# Sheet1.net
KiCad netlist of a schematic drawn in Altium Designer
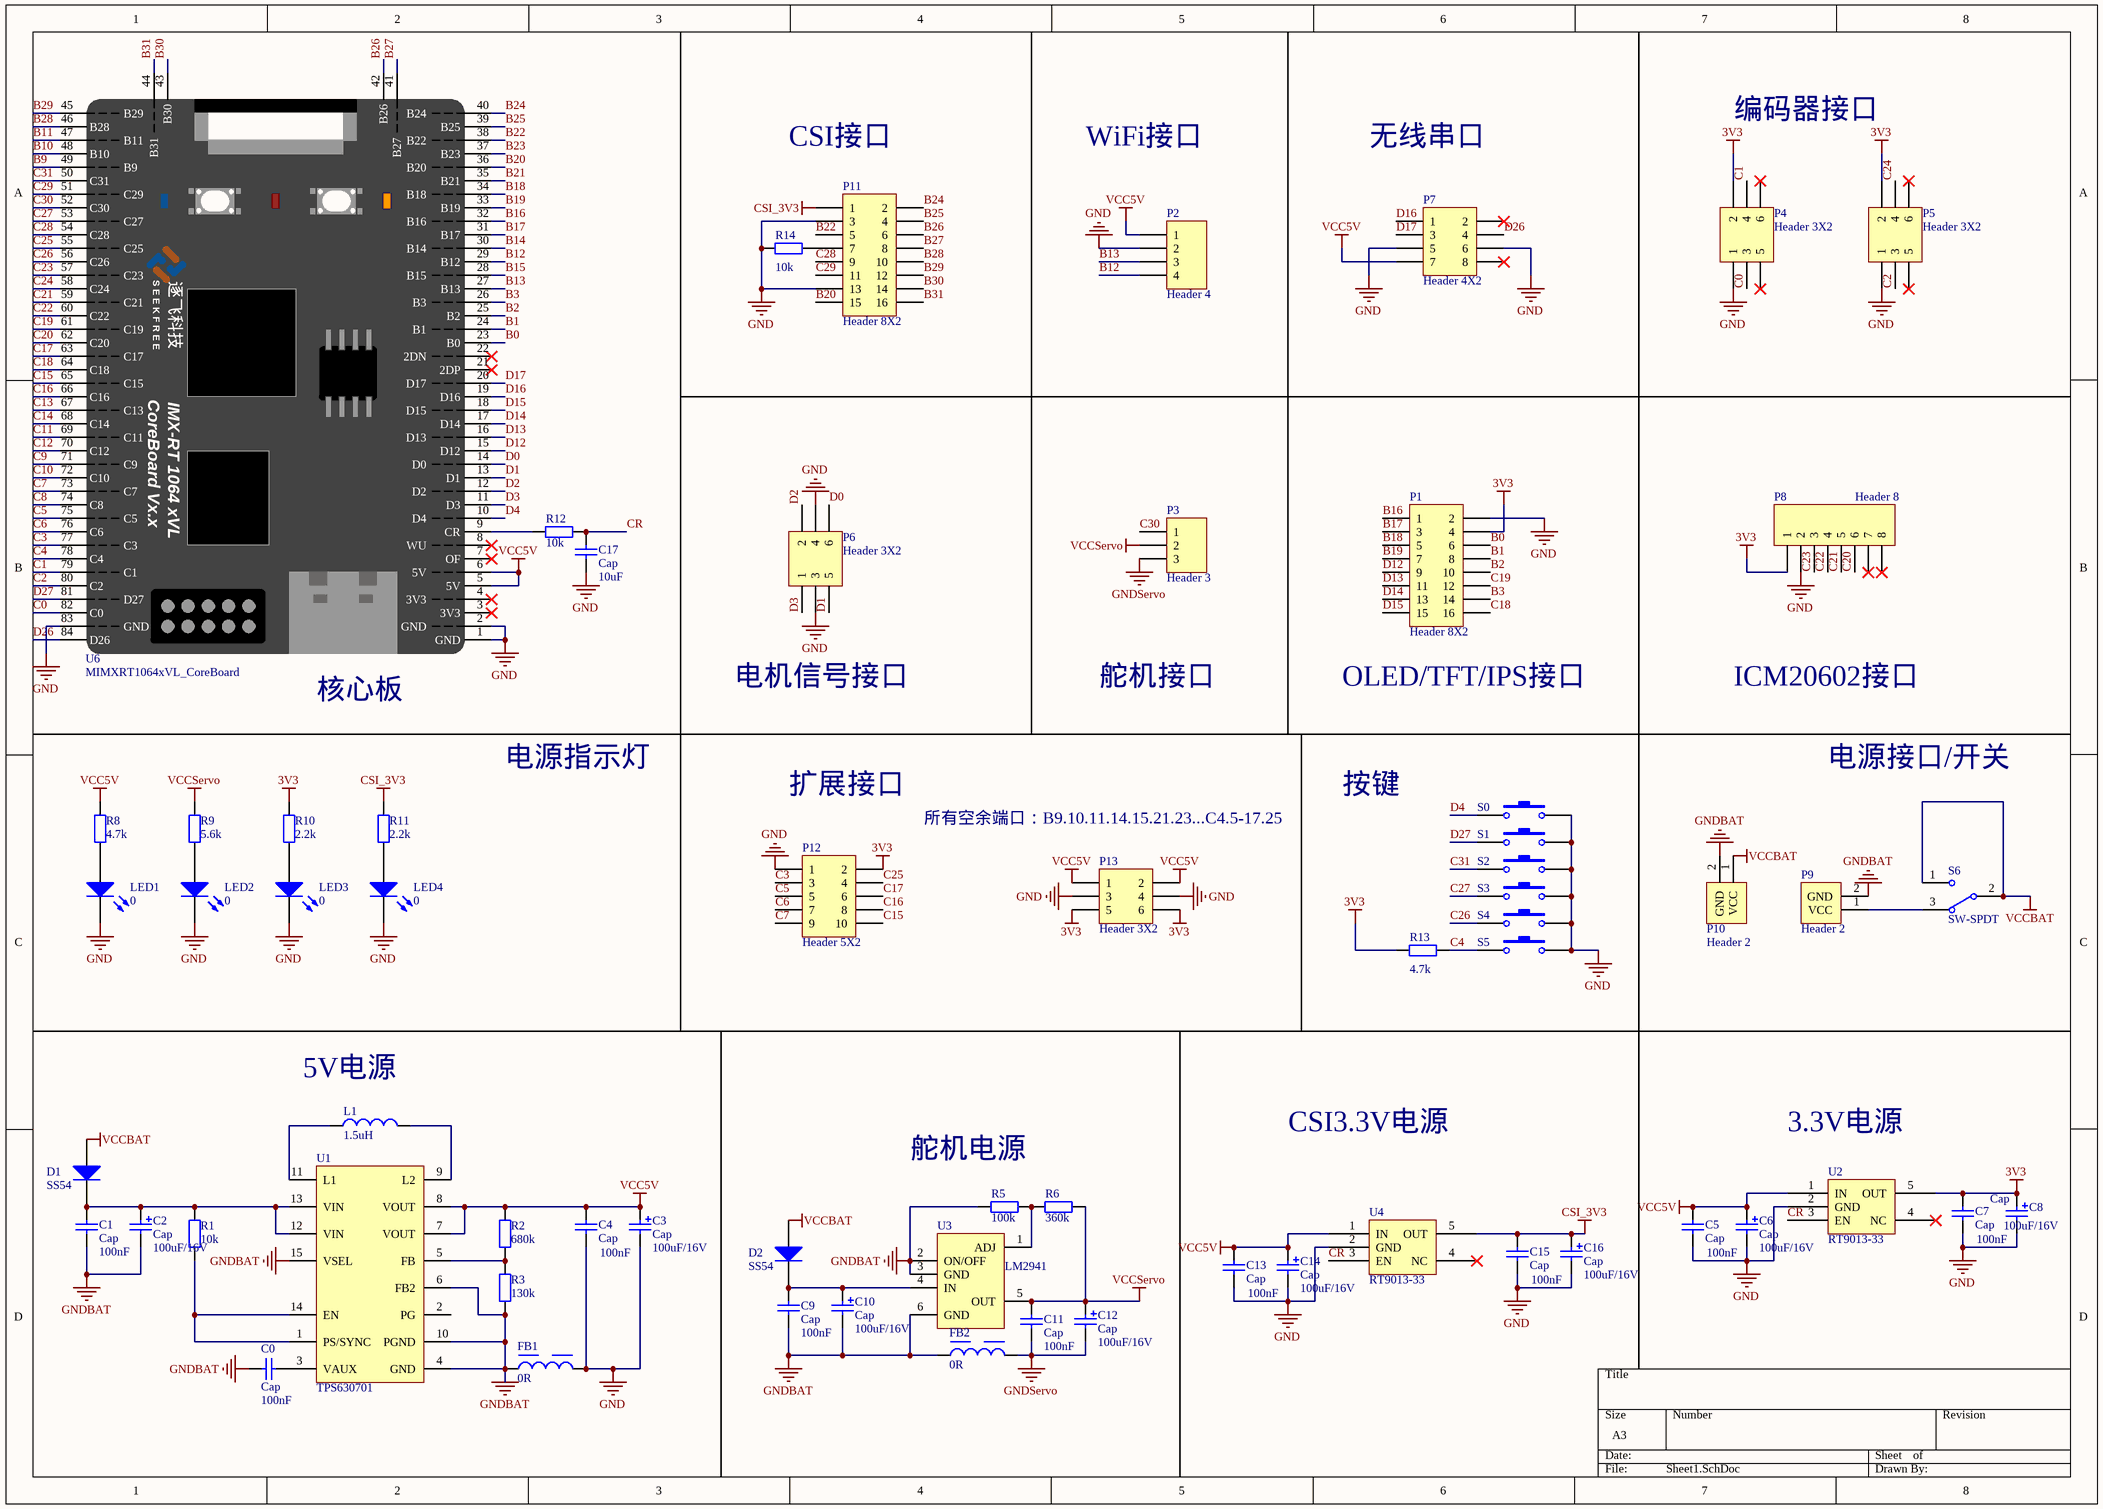
[diagram p0: Sheet1.SchDoc]

(export (version "E")
  (design (tool "Eeschema 10.0.6"))
  (components
    (comp (ref "C0")
      (value "Cap")
      (footprint "0603C")
      (description "Capacitor")
      (fields (field (name "ALTIUM_VALUE") "100nF") (field (name "PUBLISHER") "Altium Limited"))
      (libsource (lib "Schlib1") (part "Cap"))
    )
    (comp (ref "C1")
      (value "Cap")
      (footprint "0603C")
      (description "Capacitor")
      (fields (field (name "ALTIUM_VALUE") "100nF") (field (name "PUBLISHER") "Altium Limited"))
      (libsource (lib "Schlib1") (part "Cap"))
    )
    (comp (ref "C2")
      (value "Cap")
      (footprint "电解电容")
      (description "Capacitor")
      (fields (field (name "ALTIUM_VALUE") "100uF/16V") (field (name "PUBLISHER") "Altium Limited"))
      (libsource (lib "Schlib1") (part "Cap2"))
    )
    (comp (ref "C3")
      (value "Cap")
      (footprint "电解电容")
      (description "Capacitor")
      (fields (field (name "ALTIUM_VALUE") "100uF/16V") (field (name "PUBLISHER") "Altium Limited"))
      (libsource (lib "Schlib1") (part "Cap2"))
    )
    (comp (ref "C4")
      (value "Cap")
      (footprint "0603C")
      (description "Capacitor")
      (fields (field (name "ALTIUM_VALUE") "100nF") (field (name "PUBLISHER") "Altium Limited"))
      (libsource (lib "Schlib1") (part "Cap"))
    )
    (comp (ref "C5")
      (value "Cap")
      (footprint "0603C")
      (description "Capacitor")
      (fields (field (name "ALTIUM_VALUE") "100nF") (field (name "PUBLISHER") "Altium Limited"))
      (libsource (lib "Schlib1") (part "Cap"))
    )
    (comp (ref "C6")
      (value "Cap")
      (footprint "电解电容")
      (description "Capacitor")
      (fields (field (name "ALTIUM_VALUE") "100uF/16V") (field (name "PUBLISHER") "Altium Limited"))
      (libsource (lib "Schlib1") (part "Cap2"))
    )
    (comp (ref "C7")
      (value "Cap")
      (footprint "0603C")
      (description "Capacitor")
      (fields (field (name "ALTIUM_VALUE") "100nF") (field (name "PUBLISHER") "Altium Limited"))
      (libsource (lib "Schlib1") (part "Cap"))
    )
    (comp (ref "C8")
      (value "Cap")
      (footprint "电解电容")
      (description "Capacitor")
      (fields (field (name "ALTIUM_VALUE") "100uF/16V") (field (name "PUBLISHER") "Altium Limited"))
      (libsource (lib "Schlib1") (part "Cap2"))
    )
    (comp (ref "C9")
      (value "Cap")
      (footprint "0603C")
      (description "Capacitor")
      (fields (field (name "ALTIUM_VALUE") "100nF") (field (name "PUBLISHER") "Altium Limited"))
      (libsource (lib "Schlib1") (part "Cap"))
    )
    (comp (ref "C10")
      (value "Cap")
      (footprint "电解电容")
      (description "Capacitor")
      (fields (field (name "ALTIUM_VALUE") "100uF/16V") (field (name "PUBLISHER") "Altium Limited"))
      (libsource (lib "Schlib1") (part "Cap2"))
    )
    (comp (ref "C11")
      (value "Cap")
      (footprint "0603C")
      (description "Capacitor")
      (fields (field (name "ALTIUM_VALUE") "100nF") (field (name "PUBLISHER") "Altium Limited"))
      (libsource (lib "Schlib1") (part "Cap"))
    )
    (comp (ref "C12")
      (value "Cap")
      (footprint "电解电容")
      (description "Capacitor")
      (fields (field (name "ALTIUM_VALUE") "100uF/16V") (field (name "PUBLISHER") "Altium Limited"))
      (libsource (lib "Schlib1") (part "Cap2"))
    )
    (comp (ref "C13")
      (value "Cap")
      (footprint "0603C")
      (description "Capacitor")
      (fields (field (name "ALTIUM_VALUE") "100nF") (field (name "PUBLISHER") "Altium Limited"))
      (libsource (lib "Schlib1") (part "Cap"))
    )
    (comp (ref "C14")
      (value "Cap")
      (footprint "电解电容")
      (description "Capacitor")
      (fields (field (name "ALTIUM_VALUE") "100uF/16V") (field (name "PUBLISHER") "Altium Limited"))
      (libsource (lib "Schlib1") (part "Cap2"))
    )
    (comp (ref "C15")
      (value "Cap")
      (footprint "0603C")
      (description "Capacitor")
      (fields (field (name "ALTIUM_VALUE") "100nF") (field (name "PUBLISHER") "Altium Limited"))
      (libsource (lib "Schlib1") (part "Cap"))
    )
    (comp (ref "C16")
      (value "Cap")
      (footprint "电解电容")
      (description "Capacitor")
      (fields (field (name "ALTIUM_VALUE") "100uF/16V") (field (name "PUBLISHER") "Altium Limited"))
      (libsource (lib "Schlib1") (part "Cap2"))
    )
    (comp (ref "C17")
      (value "Cap")
      (footprint "0603C")
      (description "Capacitor")
      (fields (field (name "ALTIUM_VALUE") "10uF") (field (name "PUBLISHER") "Altium Limited"))
      (libsource (lib "Schlib1") (part "Cap"))
    )
    (comp (ref "D1")
      (value "SS54")
      (footprint "ss54")
      (description "Default Diode")
      (fields (field (name "PUBLISHER") "Altium Limited"))
      (libsource (lib "Schlib1") (part "Diode_1"))
    )
    (comp (ref "D2")
      (value "SS54")
      (footprint "ss54")
      (description "Default Diode")
      (fields (field (name "PUBLISHER") "Altium Limited"))
      (libsource (lib "Schlib1") (part "Diode_1"))
    )
    (comp (ref "FB1")
      (value "0R")
      (footprint "0805")
      (description "Inductor")
      (fields (field (name "PUBLISHER") "Altium Limited"))
      (libsource (lib "Schlib1") (part "FB"))
    )
    (comp (ref "FB2")
      (value "0R")
      (footprint "0805")
      (description "Inductor")
      (fields (field (name "PUBLISHER") "Altium Limited"))
      (libsource (lib "Schlib1") (part "FB"))
    )
    (comp (ref "L1")
      (value "1.5uH")
      (footprint "1R5")
      (description "Inductor")
      (fields (field (name "PUBLISHER") "Altium Limited"))
      (libsource (lib "Schlib1") (part "Inductor_2"))
    )
    (comp (ref "LED1")
      (value "0")
      (footprint "0603C")
      (description "Typical RED, GREEN, YELLOW, AMBER GaAs LED")
      (fields (field (name "PUBLISHER") "Altium Limited"))
      (libsource (lib "Schlib1") (part "LED2"))
    )
    (comp (ref "LED2")
      (value "0")
      (footprint "0603C")
      (description "Typical RED, GREEN, YELLOW, AMBER GaAs LED")
      (fields (field (name "PUBLISHER") "Altium Limited"))
      (libsource (lib "Schlib1") (part "LED2"))
    )
    (comp (ref "LED3")
      (value "0")
      (footprint "0603C")
      (description "Typical RED, GREEN, YELLOW, AMBER GaAs LED")
      (fields (field (name "PUBLISHER") "Altium Limited"))
      (libsource (lib "Schlib1") (part "LED2"))
    )
    (comp (ref "LED4")
      (value "0")
      (footprint "0603C")
      (description "Typical RED, GREEN, YELLOW, AMBER GaAs LED")
      (fields (field (name "PUBLISHER") "Altium Limited"))
      (libsource (lib "Schlib1") (part "LED2"))
    )
    (comp (ref "P1")
      (value "Header 8X2")
      (footprint "HDR2X8")
      (description "Header, 8-Pin, Dual row")
      (fields (field (name "PUBLISHER") "Altium Limited"))
      (libsource (lib "Miscellaneous Connectors") (part "Header 8X2"))
    )
    (comp (ref "P2")
      (value "Header 4")
      (footprint "HDR1X4")
      (description "Header, 4-Pin")
      (fields (field (name "PUBLISHER") "Altium Limited"))
      (libsource (lib "Miscellaneous Connectors") (part "Header 4"))
    )
    (comp (ref "P3")
      (value "Header 3")
      (footprint "HDR1X3")
      (description "Header, 3-Pin")
      (fields (field (name "PUBLISHER") "Altium Limited"))
      (libsource (lib "Miscellaneous Connectors") (part "Header 3"))
    )
    (comp (ref "P4")
      (value "Header 3X2")
      (footprint "HDR2X3")
      (description "Header, 3-Pin, Dual row")
      (fields (field (name "PUBLISHER") "Altium Limited"))
      (libsource (lib "") (part "Header 3X2_1"))
    )
    (comp (ref "P5")
      (value "Header 3X2")
      (footprint "HDR2X3")
      (description "Header, 3-Pin, Dual row")
      (fields (field (name "PUBLISHER") "Altium Limited"))
      (libsource (lib "") (part "Header 3X2_1"))
    )
    (comp (ref "P6")
      (value "Header 3X2")
      (footprint "HDR2X3")
      (description "Header, 3-Pin, Dual row")
      (fields (field (name "PUBLISHER") "Altium Limited"))
      (libsource (lib "") (part "Header 3X2_1"))
    )
    (comp (ref "P7")
      (value "Header 4X2")
      (footprint "HDR2X4")
      (description "Header, 4-Pin, Dual row")
      (fields (field (name "PUBLISHER") "Altium Limited"))
      (libsource (lib "Miscellaneous Connectors") (part "Header 4X2"))
    )
    (comp (ref "P8")
      (value "Header 8")
      (footprint "HDR1X8")
      (description "Header, 8-Pin")
      (fields (field (name "PUBLISHER") "Altium Limited"))
      (libsource (lib "Miscellaneous Connectors") (part "Header 8"))
    )
    (comp (ref "P9")
      (value "Header 2")
      (footprint "VCCBAT")
      (description "Header, 2-Pin")
      (fields (field (name "PUBLISHER") "Altium Limited"))
      (libsource (lib "Schlib1") (part "Header 2_1"))
    )
    (comp (ref "P10")
      (value "Header 2")
      (footprint "VCCBAT")
      (description "Header, 2-Pin")
      (fields (field (name "PUBLISHER") "Altium Limited"))
      (libsource (lib "Schlib1") (part "Header 2_2"))
    )
    (comp (ref "P11")
      (value "Header 8X2")
      (footprint "HDR2X8")
      (description "Header, 8-Pin, Dual row")
      (fields (field (name "PUBLISHER") "Altium Limited"))
      (libsource (lib "Miscellaneous Connectors") (part "Header 8X2"))
    )
    (comp (ref "P12")
      (value "Header 5X2")
      (footprint "HDR2X5")
      (description "Header, 5-Pin, Dual row")
      (fields (field (name "PUBLISHER") "Altium Limited"))
      (libsource (lib "Miscellaneous Connectors") (part "Header 5X2"))
    )
    (comp (ref "P13")
      (value "Header 3X2")
      (footprint "HDR2X3")
      (description "Header, 3-Pin, Dual row")
      (fields (field (name "PUBLISHER") "Altium Limited"))
      (libsource (lib "Miscellaneous Connectors") (part "Header 3X2"))
    )
    (comp (ref "R1")
      (value "10k")
      (footprint "0603R")
      (description "Resistor")
      (fields (field (name "Comment") "Res2") (field (name "PUBLISHER") "Altium Limited"))
      (libsource (lib "Schlib1") (part "Res2"))
    )
    (comp (ref "R2")
      (value "680k")
      (footprint "0603R")
      (description "Resistor")
      (fields (field (name "Comment") "Res2") (field (name "PUBLISHER") "Altium Limited"))
      (libsource (lib "Schlib1") (part "Res2"))
    )
    (comp (ref "R3")
      (value "130k")
      (footprint "0603R")
      (description "Resistor 改成了120k")
      (fields (field (name "Comment") "Res2") (field (name "PUBLISHER") "Altium Limited"))
      (libsource (lib "Schlib1") (part "Res2"))
    )
    (comp (ref "R5")
      (value "100k")
      (footprint "0603R")
      (description "Resistor")
      (fields (field (name "Comment") "Res2") (field (name "PUBLISHER") "Altium Limited"))
      (libsource (lib "") (part "Res2_1"))
    )
    (comp (ref "R6")
      (value "360k")
      (footprint "0603R")
      (description "Resistor 改成了330k")
      (fields (field (name "Comment") "Res2") (field (name "PUBLISHER") "Altium Limited"))
      (libsource (lib "") (part "Res2_1"))
    )
    (comp (ref "R8")
      (value "4.7k")
      (footprint "0603R")
      (description "Resistor")
      (fields (field (name "Comment") "Res2") (field (name "PUBLISHER") "Altium Limited"))
      (libsource (lib "Schlib1") (part "Res2"))
    )
    (comp (ref "R9")
      (value "5.6k")
      (footprint "0603R")
      (description "Resistor改成了5.1k")
      (fields (field (name "Comment") "Res2") (field (name "PUBLISHER") "Altium Limited"))
      (libsource (lib "Schlib1") (part "Res2"))
    )
    (comp (ref "R10")
      (value "2.2k")
      (footprint "0603R")
      (description "Resistor")
      (fields (field (name "Comment") "Res2") (field (name "PUBLISHER") "Altium Limited"))
      (libsource (lib "Schlib1") (part "Res2"))
    )
    (comp (ref "R11")
      (value "2.2k")
      (footprint "0603R")
      (description "Resistor")
      (fields (field (name "Comment") "Res2") (field (name "PUBLISHER") "Altium Limited"))
      (libsource (lib "Schlib1") (part "Res2"))
    )
    (comp (ref "R12")
      (value "10k")
      (footprint "0603R")
      (description "Resistor")
      (fields (field (name "Comment") "Res2") (field (name "PUBLISHER") "Altium Limited"))
      (libsource (lib "") (part "Res2_1"))
    )
    (comp (ref "R13")
      (value "4.7k")
      (footprint "0603R")
      (description "Resistor")
      (fields (field (name "Comment") "Res2") (field (name "PUBLISHER") "Altium Limited"))
      (libsource (lib "") (part "Res2_1"))
    )
    (comp (ref "R14")
      (value "10k")
      (footprint "0603R")
      (description "Resistor")
      (fields (field (name "Comment") "Res2") (field (name "PUBLISHER") "Altium Limited"))
      (libsource (lib "") (part "Res2_1"))
    )
    (comp (ref "S0")
      (value "~")
      (footprint "SPST-2")
      (description "Switch")
      (fields (field (name "PUBLISHER") "Altium Limited"))
      (libsource (lib "Miscellaneous Devices") (part "SW-PB"))
    )
    (comp (ref "S1")
      (value "~")
      (footprint "SPST-2")
      (description "Switch")
      (fields (field (name "PUBLISHER") "Altium Limited"))
      (libsource (lib "Miscellaneous Devices") (part "SW-PB"))
    )
    (comp (ref "S2")
      (value "~")
      (footprint "SPST-2")
      (description "Switch")
      (fields (field (name "PUBLISHER") "Altium Limited"))
      (libsource (lib "Miscellaneous Devices") (part "SW-PB"))
    )
    (comp (ref "S3")
      (value "~")
      (footprint "SPST-2")
      (description "Switch")
      (fields (field (name "PUBLISHER") "Altium Limited"))
      (libsource (lib "Miscellaneous Devices") (part "SW-PB"))
    )
    (comp (ref "S4")
      (value "~")
      (footprint "SPST-2")
      (description "Switch")
      (fields (field (name "PUBLISHER") "Altium Limited"))
      (libsource (lib "Miscellaneous Devices") (part "SW-PB"))
    )
    (comp (ref "S5")
      (value "~")
      (footprint "SPST-2")
      (description "Switch")
      (fields (field (name "PUBLISHER") "Altium Limited"))
      (libsource (lib "Miscellaneous Devices") (part "SW-PB"))
    )
    (comp (ref "S6")
      (value "SW-SPDT")
      (footprint "SW")
      (description "SPDT Subminiature Toggle Switch, Right Angle Mounting, Vertical Actuation")
      (fields (field (name "PUBLISHER") "Altium Limited"))
      (libsource (lib "Miscellaneous Devices") (part "SW-SPDT"))
    )
    (comp (ref "U1") (value "TPS630701") (footprint "63070") (libsource (lib "Schlib1") (part "TPS630701")))
    (comp (ref "U2")
      (value "RT9013-33")
      (footprint "SOT23-5_L")
      (libsource (lib "Schlib1") (part "RT9013-33"))
    )
    (comp (ref "U3")
      (value "LM2941")
      (footprint "TO-263-5L")
      (description "Header, 4-Pin")
      (fields (field (name "PUBLISHER") "Altium Limited"))
      (libsource (lib "Schlib1") (part "LM2941"))
    )
    (comp (ref "U4")
      (value "RT9013-33")
      (footprint "SOT23-5_L")
      (libsource (lib "Schlib1") (part "RT9013-33"))
    )
    (comp (ref "U6")
      (value "MIMXRT1064xVL_CoreBoard")
      (footprint "MIMXRT1064xVL_CoreBoard")
      (description "逐飞科技i.MX RT1064核心板整体原理，可直接使用")
      (libsource (lib "RT1064 V1.2核心板原理库") (part "MIMXRT1064xVL_CoreBoard"))
    )
  )
  (nets
    (net (code "1") (name "/B0") (class "Default")
      (node (ref "P1") (pin "6") (pinfunction "6_6") (pintype "passive"))
      (node (ref "U6") (pin "23") (pinfunction "B0_23") (pintype "passive"))
    )
    (net (code "2") (name "/B1") (class "Default")
      (node (ref "P1") (pin "8") (pinfunction "8_8") (pintype "passive"))
      (node (ref "U6") (pin "24") (pinfunction "B1_24") (pintype "passive"))
    )
    (net (code "3") (name "/B2") (class "Default")
      (node (ref "P1") (pin "10") (pinfunction "10_10") (pintype "passive"))
      (node (ref "U6") (pin "25") (pinfunction "B2_25") (pintype "passive"))
    )
    (net (code "4") (name "/B3") (class "Default")
      (node (ref "P1") (pin "14") (pinfunction "14_14") (pintype "passive"))
      (node (ref "U6") (pin "26") (pinfunction "B3_26") (pintype "passive"))
    )
    (net (code "5") (name "/B9") (class "Default")
      (node (ref "U6") (pin "49") (pinfunction "B9_49") (pintype "passive"))
    )
    (net (code "6") (name "/B10") (class "Default")
      (node (ref "U6") (pin "48") (pinfunction "B10_48") (pintype "passive"))
    )
    (net (code "7") (name "/B11") (class "Default")
      (node (ref "U6") (pin "47") (pinfunction "B11_47") (pintype "passive"))
    )
    (net (code "8") (name "/B12") (class "Default")
      (node (ref "P2") (pin "4") (pinfunction "4_4") (pintype "passive"))
      (node (ref "U6") (pin "29") (pinfunction "B12_29") (pintype "passive"))
    )
    (net (code "9") (name "/B13") (class "Default")
      (node (ref "P2") (pin "3") (pinfunction "3_3") (pintype "passive"))
      (node (ref "U6") (pin "27") (pinfunction "B13_27") (pintype "passive"))
    )
    (net (code "10") (name "/B14") (class "Default")
      (node (ref "U6") (pin "30") (pinfunction "B14_30") (pintype "passive"))
    )
    (net (code "11") (name "/B15") (class "Default")
      (node (ref "U6") (pin "28") (pinfunction "B15_28") (pintype "passive"))
    )
    (net (code "12") (name "/B16") (class "Default")
      (node (ref "P1") (pin "1") (pinfunction "1_1") (pintype "passive"))
      (node (ref "U6") (pin "32") (pinfunction "B16_32") (pintype "passive"))
    )
    (net (code "13") (name "/B17") (class "Default")
      (node (ref "P1") (pin "3") (pinfunction "3_3") (pintype "passive"))
      (node (ref "U6") (pin "31") (pinfunction "B17_31") (pintype "passive"))
    )
    (net (code "14") (name "/B18") (class "Default")
      (node (ref "P1") (pin "5") (pinfunction "5_5") (pintype "passive"))
      (node (ref "U6") (pin "34") (pinfunction "B18_34") (pintype "passive"))
    )
    (net (code "15") (name "/B19") (class "Default")
      (node (ref "P1") (pin "7") (pinfunction "7_7") (pintype "passive"))
      (node (ref "U6") (pin "33") (pinfunction "B19_33") (pintype "passive"))
    )
    (net (code "16") (name "/B20") (class "Default")
      (node (ref "P11") (pin "15") (pinfunction "15_15") (pintype "passive"))
      (node (ref "U6") (pin "36") (pinfunction "B20_36") (pintype "passive"))
    )
    (net (code "17") (name "/B21") (class "Default")
      (node (ref "U6") (pin "35") (pinfunction "B21_35") (pintype "passive"))
    )
    (net (code "18") (name "/B22") (class "Default")
      (node (ref "P11") (pin "5") (pinfunction "5_5") (pintype "passive"))
      (node (ref "U6") (pin "38") (pinfunction "B22_38") (pintype "passive"))
    )
    (net (code "19") (name "/B23") (class "Default")
      (node (ref "U6") (pin "37") (pinfunction "B23_37") (pintype "passive"))
    )
    (net (code "20") (name "/B24") (class "Default")
      (node (ref "P11") (pin "2") (pinfunction "2_2") (pintype "passive"))
      (node (ref "U6") (pin "40") (pinfunction "B24_40") (pintype "passive"))
    )
    (net (code "21") (name "/B25") (class "Default")
      (node (ref "P11") (pin "4") (pinfunction "4_4") (pintype "passive"))
      (node (ref "U6") (pin "39") (pinfunction "B25_39") (pintype "passive"))
    )
    (net (code "22") (name "/B26") (class "Default")
      (node (ref "P11") (pin "6") (pinfunction "6_6") (pintype "passive"))
      (node (ref "U6") (pin "42") (pinfunction "B26_42") (pintype "passive"))
    )
    (net (code "23") (name "/B27") (class "Default")
      (node (ref "P11") (pin "8") (pinfunction "8_8") (pintype "passive"))
      (node (ref "U6") (pin "41") (pinfunction "B27_41") (pintype "passive"))
    )
    (net (code "24") (name "/B28") (class "Default")
      (node (ref "P11") (pin "10") (pinfunction "10_10") (pintype "passive"))
      (node (ref "U6") (pin "46") (pinfunction "B28_46") (pintype "passive"))
    )
    (net (code "25") (name "/B29") (class "Default")
      (node (ref "P11") (pin "12") (pinfunction "12_12") (pintype "passive"))
      (node (ref "U6") (pin "45") (pinfunction "B29_45") (pintype "passive"))
    )
    (net (code "26") (name "/B30") (class "Default")
      (node (ref "P11") (pin "14") (pinfunction "14_14") (pintype "passive"))
      (node (ref "U6") (pin "43") (pinfunction "B30_43") (pintype "passive"))
    )
    (net (code "27") (name "/B31") (class "Default")
      (node (ref "P11") (pin "16") (pinfunction "16_16") (pintype "passive"))
      (node (ref "U6") (pin "44") (pinfunction "B31_44") (pintype "passive"))
    )
    (net (code "28") (name "/C0") (class "Default")
      (node (ref "P4") (pin "3") (pinfunction "3_3") (pintype "passive"))
      (node (ref "U6") (pin "82") (pinfunction "C0_82") (pintype "passive"))
    )
    (net (code "29") (name "/C1") (class "Default")
      (node (ref "P4") (pin "4") (pinfunction "4_4") (pintype "passive"))
      (node (ref "U6") (pin "79") (pinfunction "C1_79") (pintype "passive"))
    )
    (net (code "30") (name "/C2") (class "Default")
      (node (ref "P5") (pin "3") (pinfunction "3_3") (pintype "passive"))
      (node (ref "U6") (pin "80") (pinfunction "C2_80") (pintype "passive"))
    )
    (net (code "31") (name "/C3") (class "Default")
      (node (ref "P12") (pin "3") (pinfunction "3_3") (pintype "passive"))
      (node (ref "U6") (pin "77") (pinfunction "C3_77") (pintype "passive"))
    )
    (net (code "32") (name "/C4") (class "Default")
      (node (ref "R13") (pin "2") (pinfunction "2_2") (pintype "passive"))
      (node (ref "S5") (pin "1") (pinfunction "1_1") (pintype "passive"))
      (node (ref "U6") (pin "78") (pinfunction "C4_78") (pintype "passive"))
    )
    (net (code "33") (name "/C5") (class "Default")
      (node (ref "P12") (pin "5") (pinfunction "5_5") (pintype "passive"))
      (node (ref "U6") (pin "75") (pinfunction "C5_75") (pintype "passive"))
    )
    (net (code "34") (name "/C6") (class "Default")
      (node (ref "P12") (pin "7") (pinfunction "7_7") (pintype "passive"))
      (node (ref "U6") (pin "76") (pinfunction "C6_76") (pintype "passive"))
    )
    (net (code "35") (name "/C7") (class "Default")
      (node (ref "P12") (pin "9") (pinfunction "9_9") (pintype "passive"))
      (node (ref "U6") (pin "73") (pinfunction "C7_73") (pintype "passive"))
    )
    (net (code "36") (name "/C8") (class "Default")
      (node (ref "U6") (pin "74") (pinfunction "C8_74") (pintype "passive"))
    )
    (net (code "37") (name "/C9") (class "Default")
      (node (ref "U6") (pin "71") (pinfunction "C9_71") (pintype "passive"))
    )
    (net (code "38") (name "/C10") (class "Default")
      (node (ref "U6") (pin "72") (pinfunction "C10_72") (pintype "passive"))
    )
    (net (code "39") (name "/C11") (class "Default")
      (node (ref "U6") (pin "69") (pinfunction "C11_69") (pintype "passive"))
    )
    (net (code "40") (name "/C12") (class "Default")
      (node (ref "U6") (pin "70") (pinfunction "C12_70") (pintype "passive"))
    )
    (net (code "41") (name "/C13") (class "Default")
      (node (ref "U6") (pin "67") (pinfunction "C13_67") (pintype "passive"))
    )
    (net (code "42") (name "/C14") (class "Default")
      (node (ref "U6") (pin "68") (pinfunction "C14_68") (pintype "passive"))
    )
    (net (code "43") (name "/C15") (class "Default")
      (node (ref "P12") (pin "10") (pinfunction "10_10") (pintype "passive"))
      (node (ref "U6") (pin "65") (pinfunction "C15_65") (pintype "passive"))
    )
    (net (code "44") (name "/C16") (class "Default")
      (node (ref "P12") (pin "8") (pinfunction "8_8") (pintype "passive"))
      (node (ref "U6") (pin "66") (pinfunction "C16_66") (pintype "passive"))
    )
    (net (code "45") (name "/C17") (class "Default")
      (node (ref "P12") (pin "6") (pinfunction "6_6") (pintype "passive"))
      (node (ref "U6") (pin "63") (pinfunction "C17_63") (pintype "passive"))
    )
    (net (code "46") (name "/C18") (class "Default")
      (node (ref "P1") (pin "16") (pinfunction "16_16") (pintype "passive"))
      (node (ref "U6") (pin "64") (pinfunction "C18_64") (pintype "passive"))
    )
    (net (code "47") (name "/C19") (class "Default")
      (node (ref "P1") (pin "12") (pinfunction "12_12") (pintype "passive"))
      (node (ref "U6") (pin "61") (pinfunction "C19_61") (pintype "passive"))
    )
    (net (code "48") (name "/C20") (class "Default")
      (node (ref "P8") (pin "6") (pinfunction "6_6") (pintype "passive"))
      (node (ref "U6") (pin "62") (pinfunction "C20_62") (pintype "passive"))
    )
    (net (code "49") (name "/C21") (class "Default")
      (node (ref "P8") (pin "5") (pinfunction "5_5") (pintype "passive"))
      (node (ref "U6") (pin "59") (pinfunction "C21_59") (pintype "passive"))
    )
    (net (code "50") (name "/C22") (class "Default")
      (node (ref "P8") (pin "4") (pinfunction "4_4") (pintype "passive"))
      (node (ref "U6") (pin "60") (pinfunction "C22_60") (pintype "passive"))
    )
    (net (code "51") (name "/C23") (class "Default")
      (node (ref "P8") (pin "3") (pinfunction "3_3") (pintype "passive"))
      (node (ref "U6") (pin "57") (pinfunction "C23_57") (pintype "passive"))
    )
    (net (code "52") (name "/C24") (class "Default")
      (node (ref "P5") (pin "4") (pinfunction "4_4") (pintype "passive"))
      (node (ref "U6") (pin "58") (pinfunction "C24_58") (pintype "passive"))
    )
    (net (code "53") (name "/C25") (class "Default")
      (node (ref "P12") (pin "4") (pinfunction "4_4") (pintype "passive"))
      (node (ref "U6") (pin "55") (pinfunction "C25_55") (pintype "passive"))
    )
    (net (code "54") (name "/C26") (class "Default")
      (node (ref "S4") (pin "1") (pinfunction "1_1") (pintype "passive"))
      (node (ref "U6") (pin "56") (pinfunction "C26_56") (pintype "passive"))
    )
    (net (code "55") (name "/C27") (class "Default")
      (node (ref "S3") (pin "1") (pinfunction "1_1") (pintype "passive"))
      (node (ref "U6") (pin "53") (pinfunction "C27_53") (pintype "passive"))
    )
    (net (code "56") (name "/C28") (class "Default")
      (node (ref "P11") (pin "9") (pinfunction "9_9") (pintype "passive"))
      (node (ref "U6") (pin "54") (pinfunction "C28_54") (pintype "passive"))
    )
    (net (code "57") (name "/C29") (class "Default")
      (node (ref "P11") (pin "11") (pinfunction "11_11") (pintype "passive"))
      (node (ref "U6") (pin "51") (pinfunction "C29_51") (pintype "passive"))
    )
    (net (code "58") (name "/C30") (class "Default")
      (node (ref "P3") (pin "1") (pinfunction "1_1") (pintype "passive"))
      (node (ref "U6") (pin "52") (pinfunction "C30_52") (pintype "passive"))
    )
    (net (code "59") (name "/C31") (class "Default")
      (node (ref "S2") (pin "1") (pinfunction "1_1") (pintype "passive"))
      (node (ref "U6") (pin "50") (pinfunction "C31_50") (pintype "passive"))
    )
    (net (code "60") (name "/CR") (class "Default")
      (node (ref "C17") (pin "2") (pinfunction "2_2") (pintype "passive"))
      (node (ref "R12") (pin "2") (pinfunction "2_2") (pintype "passive"))
      (node (ref "U2") (pin "3") (pinfunction "EN_3") (pintype "passive"))
      (node (ref "U4") (pin "3") (pinfunction "EN_3") (pintype "passive"))
    )
    (net (code "61") (name "/D0") (class "Default")
      (node (ref "P6") (pin "6") (pinfunction "6_6") (pintype "passive"))
      (node (ref "U6") (pin "14") (pinfunction "D0_14") (pintype "passive"))
    )
    (net (code "62") (name "/D1") (class "Default")
      (node (ref "P6") (pin "5") (pinfunction "5_5") (pintype "passive"))
      (node (ref "U6") (pin "13") (pinfunction "D1_13") (pintype "passive"))
    )
    (net (code "63") (name "/D2") (class "Default")
      (node (ref "P6") (pin "2") (pinfunction "2_2") (pintype "passive"))
      (node (ref "U6") (pin "12") (pinfunction "D2_12") (pintype "passive"))
    )
    (net (code "64") (name "/D3") (class "Default")
      (node (ref "P6") (pin "1") (pinfunction "1_1") (pintype "passive"))
      (node (ref "U6") (pin "11") (pinfunction "D3_11") (pintype "passive"))
    )
    (net (code "65") (name "/D4") (class "Default")
      (node (ref "S0") (pin "1") (pinfunction "1_1") (pintype "passive"))
      (node (ref "U6") (pin "10") (pinfunction "D4_10") (pintype "passive"))
    )
    (net (code "66") (name "/D12") (class "Default")
      (node (ref "P1") (pin "9") (pinfunction "9_9") (pintype "passive"))
      (node (ref "U6") (pin "15") (pinfunction "D12_15") (pintype "passive"))
    )
    (net (code "67") (name "/D13") (class "Default")
      (node (ref "P1") (pin "11") (pinfunction "11_11") (pintype "passive"))
      (node (ref "U6") (pin "16") (pinfunction "D13_16") (pintype "passive"))
    )
    (net (code "68") (name "/D14") (class "Default")
      (node (ref "P1") (pin "13") (pinfunction "13_13") (pintype "passive"))
      (node (ref "U6") (pin "17") (pinfunction "D14_17") (pintype "passive"))
    )
    (net (code "69") (name "/D15") (class "Default")
      (node (ref "P1") (pin "15") (pinfunction "15_15") (pintype "passive"))
      (node (ref "U6") (pin "18") (pinfunction "D15_18") (pintype "passive"))
    )
    (net (code "70") (name "/D16") (class "Default")
      (node (ref "P7") (pin "1") (pinfunction "1_1") (pintype "passive"))
      (node (ref "U6") (pin "19") (pinfunction "D16_19") (pintype "passive"))
    )
    (net (code "71") (name "/D17") (class "Default")
      (node (ref "P7") (pin "3") (pinfunction "3_3") (pintype "passive"))
      (node (ref "U6") (pin "20") (pinfunction "D17_20") (pintype "passive"))
    )
    (net (code "72") (name "/D26") (class "Default")
      (node (ref "P7") (pin "4") (pinfunction "4_4") (pintype "passive"))
      (node (ref "U6") (pin "84") (pinfunction "D26_84") (pintype "passive"))
    )
    (net (code "73") (name "/D27") (class "Default")
      (node (ref "S1") (pin "1") (pinfunction "1_1") (pintype "passive"))
      (node (ref "U6") (pin "81") (pinfunction "D27_81") (pintype "passive"))
    )
    (net (code "74") (name "3V3") (class "Default")
      (node (ref "C7") (pin "2") (pinfunction "2_2") (pintype "passive"))
      (node (ref "C8") (pin "1") (pinfunction "1_1") (pintype "passive"))
      (node (ref "P1") (pin "4") (pinfunction "4_4") (pintype "passive"))
      (node (ref "P12") (pin "2") (pinfunction "2_2") (pintype "passive"))
      (node (ref "P13") (pin "5") (pinfunction "5_5") (pintype "passive"))
      (node (ref "P13") (pin "6") (pinfunction "6_6") (pintype "passive"))
      (node (ref "P4") (pin "2") (pinfunction "2_2") (pintype "passive"))
      (node (ref "P5") (pin "2") (pinfunction "2_2") (pintype "passive"))
      (node (ref "P8") (pin "1") (pinfunction "1_1") (pintype "passive"))
      (node (ref "R10") (pin "2") (pinfunction "2_2") (pintype "passive"))
      (node (ref "R13") (pin "1") (pinfunction "1_1") (pintype "passive"))
      (node (ref "U2") (pin "5") (pinfunction "OUT_5") (pintype "passive"))
    )
    (net (code "75") (name "CSI_3V3") (class "Default")
      (node (ref "C15") (pin "2") (pinfunction "2_2") (pintype "passive"))
      (node (ref "C16") (pin "1") (pinfunction "1_1") (pintype "passive"))
      (node (ref "P11") (pin "1") (pinfunction "1_1") (pintype "passive"))
      (node (ref "R11") (pin "2") (pinfunction "2_2") (pintype "passive"))
      (node (ref "U4") (pin "5") (pinfunction "OUT_5") (pintype "passive"))
    )
    (net (code "76") (name "GND") (class "Default")
      (node (ref "C13") (pin "1") (pinfunction "1_1") (pintype "passive"))
      (node (ref "C14") (pin "2") (pinfunction "2_2") (pintype "passive"))
      (node (ref "C15") (pin "1") (pinfunction "1_1") (pintype "passive"))
      (node (ref "C16") (pin "2") (pinfunction "2_2") (pintype "passive"))
      (node (ref "C17") (pin "1") (pinfunction "1_1") (pintype "passive"))
      (node (ref "C3") (pin "2") (pinfunction "2_2") (pintype "passive"))
      (node (ref "C4") (pin "1") (pinfunction "1_1") (pintype "passive"))
      (node (ref "C5") (pin "1") (pinfunction "1_1") (pintype "passive"))
      (node (ref "C6") (pin "2") (pinfunction "2_2") (pintype "passive"))
      (node (ref "C7") (pin "1") (pinfunction "1_1") (pintype "passive"))
      (node (ref "C8") (pin "2") (pinfunction "2_2") (pintype "passive"))
      (node (ref "FB1") (pin "2") (pinfunction "2_2") (pintype "passive"))
      (node (ref "LED1") (pin "2") (pinfunction "K_2") (pintype "passive"))
      (node (ref "LED2") (pin "2") (pinfunction "K_2") (pintype "passive"))
      (node (ref "LED3") (pin "2") (pinfunction "K_2") (pintype "passive"))
      (node (ref "LED4") (pin "2") (pinfunction "K_2") (pintype "passive"))
      (node (ref "P1") (pin "2") (pinfunction "2_2") (pintype "passive"))
      (node (ref "P11") (pin "13") (pinfunction "13_13") (pintype "passive"))
      (node (ref "P11") (pin "3") (pinfunction "3_3") (pintype "passive"))
      (node (ref "P12") (pin "1") (pinfunction "1_1") (pintype "passive"))
      (node (ref "P13") (pin "3") (pinfunction "3_3") (pintype "passive"))
      (node (ref "P13") (pin "4") (pinfunction "4_4") (pintype "passive"))
      (node (ref "P2") (pin "2") (pinfunction "2_2") (pintype "passive"))
      (node (ref "P4") (pin "1") (pinfunction "1_1") (pintype "passive"))
      (node (ref "P5") (pin "1") (pinfunction "1_1") (pintype "passive"))
      (node (ref "P6") (pin "3") (pinfunction "3_3") (pintype "passive"))
      (node (ref "P6") (pin "4") (pinfunction "4_4") (pintype "passive"))
      (node (ref "P7") (pin "5") (pinfunction "5_5") (pintype "passive"))
      (node (ref "P7") (pin "6") (pinfunction "6_6") (pintype "passive"))
      (node (ref "P8") (pin "2") (pinfunction "2_2") (pintype "passive"))
      (node (ref "R14") (pin "1") (pinfunction "1_1") (pintype "passive"))
      (node (ref "S0") (pin "2") (pinfunction "2_2") (pintype "passive"))
      (node (ref "S1") (pin "2") (pinfunction "2_2") (pintype "passive"))
      (node (ref "S2") (pin "2") (pinfunction "2_2") (pintype "passive"))
      (node (ref "S3") (pin "2") (pinfunction "2_2") (pintype "passive"))
      (node (ref "S4") (pin "2") (pinfunction "2_2") (pintype "passive"))
      (node (ref "S5") (pin "2") (pinfunction "2_2") (pintype "passive"))
      (node (ref "U2") (pin "2") (pinfunction "GND_2") (pintype "passive"))
      (node (ref "U4") (pin "2") (pinfunction "GND_2") (pintype "passive"))
      (node (ref "U6") (pin "1") (pinfunction "GND_1") (pintype "passive"))
      (node (ref "U6") (pin "2") (pinfunction "GND_2") (pintype "passive"))
      (node (ref "U6") (pin "83") (pinfunction "GND_83") (pintype "passive"))
    )
    (net (code "77") (name "GNDBAT") (class "Default")
      (node (ref "C0") (pin "2") (pinfunction "2_2") (pintype "passive"))
      (node (ref "C1") (pin "1") (pinfunction "1_1") (pintype "passive"))
      (node (ref "C10") (pin "2") (pinfunction "2_2") (pintype "passive"))
      (node (ref "C2") (pin "2") (pinfunction "2_2") (pintype "passive"))
      (node (ref "C9") (pin "1") (pinfunction "1_1") (pintype "passive"))
      (node (ref "FB1") (pin "1") (pinfunction "1_1") (pintype "passive"))
      (node (ref "FB2") (pin "1") (pinfunction "1_1") (pintype "passive"))
      (node (ref "P10") (pin "2") (pinfunction "GND_2") (pintype "passive"))
      (node (ref "P9") (pin "2") (pinfunction "GND_2") (pintype "passive"))
      (node (ref "R3") (pin "1") (pinfunction "1_1") (pintype "passive"))
      (node (ref "R5") (pin "1") (pinfunction "1_1") (pintype "passive"))
      (node (ref "U1") (pin "10") (pinfunction "PGND_10") (pintype "passive"))
      (node (ref "U1") (pin "15") (pinfunction "VSEL_15") (pintype "passive"))
      (node (ref "U1") (pin "4") (pinfunction "GND_4") (pintype "passive"))
      (node (ref "U1") (pin "6") (pinfunction "FB2_6") (pintype "passive"))
      (node (ref "U3") (pin "2") (pinfunction "ON/OFF_2") (pintype "passive"))
      (node (ref "U3") (pin "3") (pinfunction "GND_3") (pintype "passive"))
      (node (ref "U3") (pin "6") (pinfunction "GND_6") (pintype "passive"))
    )
    (net (code "78") (name "GNDServo") (class "Default")
      (node (ref "C11") (pin "1") (pinfunction "1_1") (pintype "passive"))
      (node (ref "C12") (pin "2") (pinfunction "2_2") (pintype "passive"))
      (node (ref "FB2") (pin "2") (pinfunction "2_2") (pintype "passive"))
      (node (ref "P3") (pin "3") (pinfunction "3_3") (pintype "passive"))
    )
    (net (code "79") (name "Net-(D1-K)") (class "Default")
      (node (ref "C1") (pin "2") (pinfunction "2_2") (pintype "passive"))
      (node (ref "C2") (pin "1") (pinfunction "1_1") (pintype "passive"))
      (node (ref "D1") (pin "2") (pinfunction "K_2") (pintype "passive"))
      (node (ref "R1") (pin "2") (pinfunction "2_2") (pintype "passive"))
      (node (ref "U1") (pin "12") (pinfunction "VIN_12") (pintype "passive"))
      (node (ref "U1") (pin "13") (pinfunction "VIN_13") (pintype "passive"))
    )
    (net (code "80") (name "Net-(D2-K)") (class "Default")
      (node (ref "C10") (pin "1") (pinfunction "1_1") (pintype "passive"))
      (node (ref "C9") (pin "2") (pinfunction "2_2") (pintype "passive"))
      (node (ref "D2") (pin "2") (pinfunction "K_2") (pintype "passive"))
      (node (ref "U3") (pin "4") (pinfunction "IN_4") (pintype "passive"))
    )
    (net (code "81") (name "Net-(LED1-A)") (class "Default")
      (node (ref "LED1") (pin "1") (pinfunction "A_1") (pintype "passive"))
      (node (ref "R8") (pin "1") (pinfunction "1_1") (pintype "passive"))
    )
    (net (code "82") (name "Net-(LED2-A)") (class "Default")
      (node (ref "LED2") (pin "1") (pinfunction "A_1") (pintype "passive"))
      (node (ref "R9") (pin "1") (pinfunction "1_1") (pintype "passive"))
    )
    (net (code "83") (name "Net-(LED3-A)") (class "Default")
      (node (ref "LED3") (pin "1") (pinfunction "A_1") (pintype "passive"))
      (node (ref "R10") (pin "1") (pinfunction "1_1") (pintype "passive"))
    )
    (net (code "84") (name "Net-(LED4-A)") (class "Default")
      (node (ref "LED4") (pin "1") (pinfunction "A_1") (pintype "passive"))
      (node (ref "R11") (pin "1") (pinfunction "1_1") (pintype "passive"))
    )
    (net (code "85") (name "Net-(P9-VCC)") (class "Default")
      (node (ref "P9") (pin "1") (pinfunction "VCC_1") (pintype "passive"))
      (node (ref "S6") (pin "3") (pinfunction "3_3") (pintype "passive"))
    )
    (net (code "86") (name "Net-(P11-Pad7)") (class "Default")
      (node (ref "P11") (pin "7") (pinfunction "7_7") (pintype "passive"))
      (node (ref "R14") (pin "2") (pinfunction "2_2") (pintype "passive"))
    )
    (net (code "87") (name "Net-(U1-EN)") (class "Default")
      (node (ref "R1") (pin "1") (pinfunction "1_1") (pintype "passive"))
      (node (ref "U1") (pin "1") (pinfunction "PS/SYNC_1") (pintype "passive"))
      (node (ref "U1") (pin "14") (pinfunction "EN_14") (pintype "passive"))
    )
    (net (code "88") (name "Net-(U1-FB)") (class "Default")
      (node (ref "R2") (pin "1") (pinfunction "1_1") (pintype "passive"))
      (node (ref "R3") (pin "2") (pinfunction "2_2") (pintype "passive"))
      (node (ref "U1") (pin "5") (pinfunction "FB_5") (pintype "passive"))
    )
    (net (code "89") (name "Net-(U1-L1)") (class "Default")
      (node (ref "L1") (pin "1") (pinfunction "1_1") (pintype "passive"))
      (node (ref "U1") (pin "11") (pinfunction "L1_11") (pintype "passive"))
    )
    (net (code "90") (name "Net-(U1-L2)") (class "Default")
      (node (ref "L1") (pin "2") (pinfunction "2_2") (pintype "passive"))
      (node (ref "U1") (pin "9") (pinfunction "L2_9") (pintype "passive"))
    )
    (net (code "91") (name "Net-(U1-VAUX)") (class "Default")
      (node (ref "C0") (pin "1") (pinfunction "1_1") (pintype "passive"))
      (node (ref "U1") (pin "3") (pinfunction "VAUX_3") (pintype "passive"))
    )
    (net (code "92") (name "Net-(U3-ADJ)") (class "Default")
      (node (ref "R5") (pin "2") (pinfunction "2_2") (pintype "passive"))
      (node (ref "R6") (pin "1") (pinfunction "1_1") (pintype "passive"))
      (node (ref "U3") (pin "1") (pinfunction "ADJ_1") (pintype "passive"))
    )
    (net (code "93") (name "Net-(U6-CR)") (class "Default")
      (node (ref "R12") (pin "1") (pinfunction "1_1") (pintype "passive"))
      (node (ref "U6") (pin "9") (pinfunction "CR_9") (pintype "passive"))
    )
    (net (code "94") (name "VCC5V") (class "Default")
      (node (ref "C13") (pin "2") (pinfunction "2_2") (pintype "passive"))
      (node (ref "C14") (pin "1") (pinfunction "1_1") (pintype "passive"))
      (node (ref "C3") (pin "1") (pinfunction "1_1") (pintype "passive"))
      (node (ref "C4") (pin "2") (pinfunction "2_2") (pintype "passive"))
      (node (ref "C5") (pin "2") (pinfunction "2_2") (pintype "passive"))
      (node (ref "C6") (pin "1") (pinfunction "1_1") (pintype "passive"))
      (node (ref "P13") (pin "1") (pinfunction "1_1") (pintype "passive"))
      (node (ref "P13") (pin "2") (pinfunction "2_2") (pintype "passive"))
      (node (ref "P2") (pin "1") (pinfunction "1_1") (pintype "passive"))
      (node (ref "P7") (pin "7") (pinfunction "7_7") (pintype "passive"))
      (node (ref "R2") (pin "2") (pinfunction "2_2") (pintype "passive"))
      (node (ref "R8") (pin "2") (pinfunction "2_2") (pintype "passive"))
      (node (ref "U1") (pin "7") (pinfunction "VOUT_7") (pintype "passive"))
      (node (ref "U1") (pin "8") (pinfunction "VOUT_8") (pintype "passive"))
      (node (ref "U2") (pin "1") (pinfunction "IN_1") (pintype "passive"))
      (node (ref "U4") (pin "1") (pinfunction "IN_1") (pintype "passive"))
      (node (ref "U6") (pin "5") (pinfunction "5V_5") (pintype "passive"))
      (node (ref "U6") (pin "6") (pinfunction "5V_6") (pintype "passive"))
    )
    (net (code "95") (name "VCCBAT") (class "Default")
      (node (ref "D1") (pin "1") (pinfunction "A_1") (pintype "passive"))
      (node (ref "D2") (pin "1") (pinfunction "A_1") (pintype "passive"))
      (node (ref "P10") (pin "1") (pinfunction "VCC_1") (pintype "passive"))
      (node (ref "S6") (pin "1") (pinfunction "1_1") (pintype "passive"))
      (node (ref "S6") (pin "2") (pinfunction "2_2") (pintype "passive"))
    )
    (net (code "96") (name "VCCServo") (class "Default")
      (node (ref "C11") (pin "2") (pinfunction "2_2") (pintype "passive"))
      (node (ref "C12") (pin "1") (pinfunction "1_1") (pintype "passive"))
      (node (ref "P3") (pin "2") (pinfunction "2_2") (pintype "passive"))
      (node (ref "R6") (pin "2") (pinfunction "2_2") (pintype "passive"))
      (node (ref "R9") (pin "2") (pinfunction "2_2") (pintype "passive"))
      (node (ref "U3") (pin "5") (pinfunction "OUT_5") (pintype "passive"))
    )
    (net (code "97") (name "unconnected-(P4-Pad5)") (class "Default")
      (node (ref "P4") (pin "5") (pinfunction "5_5") (pintype "passive+no_connect"))
    )
    (net (code "98") (name "unconnected-(P4-Pad6)") (class "Default")
      (node (ref "P4") (pin "6") (pinfunction "6_6") (pintype "passive+no_connect"))
    )
    (net (code "99") (name "unconnected-(P5-Pad5)") (class "Default")
      (node (ref "P5") (pin "5") (pinfunction "5_5") (pintype "passive+no_connect"))
    )
    (net (code "100") (name "unconnected-(P5-Pad6)") (class "Default")
      (node (ref "P5") (pin "6") (pinfunction "6_6") (pintype "passive+no_connect"))
    )
    (net (code "101") (name "unconnected-(P7-Pad2)") (class "Default")
      (node (ref "P7") (pin "2") (pinfunction "2_2") (pintype "passive+no_connect"))
    )
    (net (code "102") (name "unconnected-(P7-Pad8)") (class "Default")
      (node (ref "P7") (pin "8") (pinfunction "8_8") (pintype "passive+no_connect"))
    )
    (net (code "103") (name "unconnected-(P8-Pad7)") (class "Default")
      (node (ref "P8") (pin "7") (pinfunction "7_7") (pintype "passive+no_connect"))
    )
    (net (code "104") (name "unconnected-(P8-Pad8)") (class "Default")
      (node (ref "P8") (pin "8") (pinfunction "8_8") (pintype "passive+no_connect"))
    )
    (net (code "105") (name "unconnected-(U1-PG-Pad2)") (class "Default")
      (node (ref "U1") (pin "2") (pinfunction "PG_2") (pintype "passive"))
    )
    (net (code "106") (name "unconnected-(U2-NC-Pad4)") (class "Default")
      (node (ref "U2") (pin "4") (pinfunction "NC_4") (pintype "passive+no_connect"))
    )
    (net (code "107") (name "unconnected-(U4-NC-Pad4)") (class "Default")
      (node (ref "U4") (pin "4") (pinfunction "NC_4") (pintype "passive+no_connect"))
    )
    (net (code "108") (name "unconnected-(U6-2DN-Pad22)") (class "Default")
      (node (ref "U6") (pin "22") (pinfunction "2DN_22") (pintype "passive+no_connect"))
    )
    (net (code "109") (name "unconnected-(U6-2DP-Pad21)") (class "Default")
      (node (ref "U6") (pin "21") (pinfunction "2DP_21") (pintype "passive+no_connect"))
    )
    (net (code "110") (name "unconnected-(U6-3V3-Pad3)") (class "Default")
      (node (ref "U6") (pin "3") (pinfunction "3V3_3") (pintype "passive+no_connect"))
    )
    (net (code "111") (name "unconnected-(U6-3V3-Pad4)") (class "Default")
      (node (ref "U6") (pin "4") (pinfunction "3V3_4") (pintype "passive+no_connect"))
    )
    (net (code "112") (name "unconnected-(U6-OF-Pad7)") (class "Default")
      (node (ref "U6") (pin "7") (pinfunction "OF_7") (pintype "passive+no_connect"))
    )
    (net (code "113") (name "unconnected-(U6-WU-Pad8)") (class "Default")
      (node (ref "U6") (pin "8") (pinfunction "WU_8") (pintype "passive+no_connect"))
    )
  )
)
